# kiceker_board.net
KiCad netlist of a schematic drawn in EAGLE
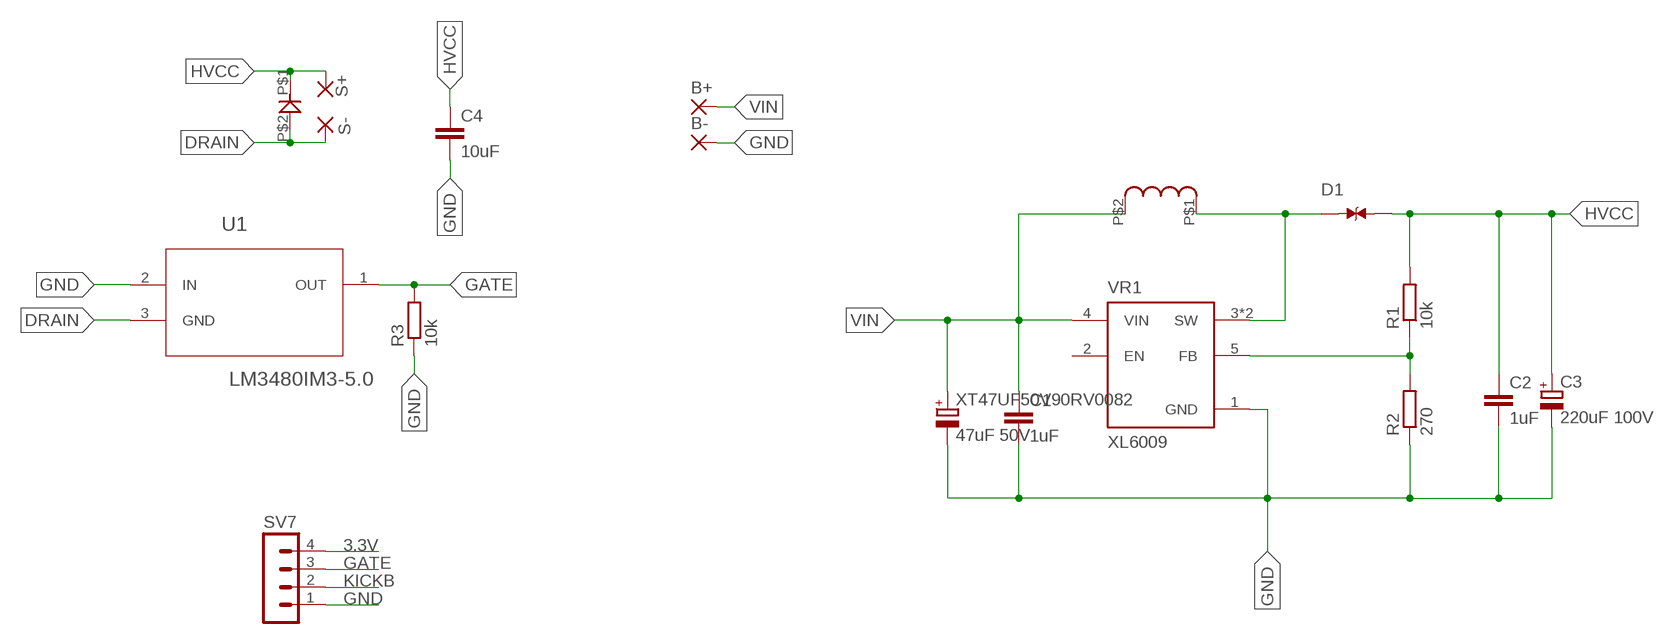
[diagram p0: schematic, sheet 1]

(export (version "E")
  (design (tool "Eeschema 10.0.6"))
  (components
    (comp (ref "B+")
      (value "3,81/1,4")
      (footprint "eagle-import:3,81_1,4")
      (libsource (lib "eagle-import") (part "3,81/1,4"))
    )
    (comp (ref "B-")
      (value "3,81/1,4")
      (footprint "eagle-import:3,81_1,4")
      (libsource (lib "eagle-import") (part "3,81/1,4"))
    )
    (comp (ref "C1")
      (value "1uF")
      (footprint "eagle-import:C0603")
      (libsource (lib "eagle-import") (part "C-EUC0603"))
    )
    (comp (ref "C2")
      (value "1uF")
      (footprint "eagle-import:C0603")
      (libsource (lib "eagle-import") (part "C-EUC0603"))
    )
    (comp (ref "C3")
      (value "220uF 100V")
      (footprint "eagle-import:E5-5")
      (libsource (lib "eagle-import") (part "CPOL-EUE5-5"))
    )
    (comp (ref "C4")
      (value "10uF")
      (footprint "eagle-import:C0603")
      (libsource (lib "eagle-import") (part "C-EUC0603"))
    )
    (comp (ref "D1")
      (value "SMCJ15CA_V7G")
      (footprint "eagle-import:DIOM6859X262N")
      (fields (field (name "MF") "Taiwan Semiconductor") (field (name "MP") "SMCJ15CA V7G"))
      (libsource (lib "eagle-import") (part "SMCJ15CA_V7G"))
    )
    (comp (ref "R1")
      (value "10k")
      (footprint "eagle-import:R0603")
      (libsource (lib "eagle-import") (part "R-EU_R0603"))
    )
    (comp (ref "R2")
      (value "270")
      (footprint "eagle-import:R0603")
      (libsource (lib "eagle-import") (part "R-EU_R0603"))
    )
    (comp (ref "R3")
      (value "10k")
      (footprint "eagle-import:R0603")
      (libsource (lib "eagle-import") (part "R-EU_R0603"))
    )
    (comp (ref "S+")
      (value "3,81/1,4")
      (footprint "eagle-import:3,81_1,4")
      (libsource (lib "eagle-import") (part "3,81/1,4"))
    )
    (comp (ref "S-")
      (value "3,81/1,4")
      (footprint "eagle-import:3,81_1,4")
      (libsource (lib "eagle-import") (part "3,81/1,4"))
    )
    (comp (ref "SV7")
      (value "MA04-1")
      (footprint "eagle-import:MA04-1")
      (libsource (lib "eagle-import") (part "MA04-1"))
    )
    (comp (ref "U$1")
      (value "TMPC1265")
      (footprint "eagle-import:TMPC1265")
      (libsource (lib "eagle-import") (part "TMPC1265"))
    )
    (comp (ref "U$2")
      (value "SMBF")
      (footprint "eagle-import:SMBF")
      (libsource (lib "eagle-import") (part "SMBF"))
    )
    (comp (ref "U1")
      (value "LM3480IM3-5.0")
      (footprint "eagle-import:SOT95P263X110-3N")
      (fields (field (name "MF") "Texas") (field (name "MP") "LM3480IM3-5.0/NOPB"))
      (libsource (lib "eagle-import") (part "LM3480IM3-5.0"))
    )
    (comp (ref "VR1")
      (value "XL6009")
      (footprint "eagle-import:DPAK170P1435X465-6N")
      (fields (field (name "MF") "XLSEMI"))
      (libsource (lib "eagle-import") (part "XL6009"))
    )
    (comp (ref "XT47UF50V90RV0082")
      (value "47uF 50V")
      (footprint "eagle-import:153CLV-0605")
      (libsource (lib "eagle-import") (part "CPOL-EU153CLV-0605"))
    )
  )
  (nets
    (net (code "1") (name "/3.3V") (class "Default")
      (node (ref "SV7") (pin "4") (pinfunction "4_4") (pintype "passive"))
    )
    (net (code "2") (name "/KICKB") (class "Default")
      (node (ref "SV7") (pin "2") (pinfunction "2_2") (pintype "passive"))
    )
    (net (code "3") (name "DRAIN") (class "Default")
      (node (ref "S-") (pin "1") (pinfunction "P_1") (pintype "passive"))
      (node (ref "U$2") (pin "P$2") (pinfunction "P$1_P$2") (pintype "bidirectional"))
      (node (ref "U1") (pin "3") (pinfunction "GND_3") (pintype "passive"))
    )
    (net (code "4") (name "GATE") (class "Default")
      (node (ref "R3") (pin "2") (pinfunction "2_2") (pintype "passive"))
      (node (ref "SV7") (pin "3") (pinfunction "3_3") (pintype "passive"))
      (node (ref "U1") (pin "1") (pinfunction "OUT_1") (pintype "output"))
    )
    (net (code "5") (name "GND") (class "Default")
      (node (ref "B-") (pin "1") (pinfunction "P_1") (pintype "passive"))
      (node (ref "C1") (pin "2") (pinfunction "2_2") (pintype "passive"))
      (node (ref "C2") (pin "2") (pinfunction "2_2") (pintype "passive"))
      (node (ref "C3") (pin "-") (pinfunction "-_-") (pintype "passive"))
      (node (ref "C4") (pin "2") (pinfunction "2_2") (pintype "passive"))
      (node (ref "R2") (pin "1") (pinfunction "1_1") (pintype "passive"))
      (node (ref "R3") (pin "1") (pinfunction "1_1") (pintype "passive"))
      (node (ref "SV7") (pin "1") (pinfunction "1_1") (pintype "passive"))
      (node (ref "U1") (pin "2") (pinfunction "IN_2") (pintype "power_in"))
      (node (ref "VR1") (pin "1") (pinfunction "GND_1") (pintype "power_in"))
      (node (ref "XT47UF50V90RV0082") (pin "-") (pinfunction "-_-") (pintype "passive"))
    )
    (net (code "6") (name "HVCC") (class "Default")
      (node (ref "C2") (pin "1") (pinfunction "1_1") (pintype "passive"))
      (node (ref "C3") (pin "+") (pinfunction "+_+") (pintype "passive"))
      (node (ref "C4") (pin "1") (pinfunction "1_1") (pintype "passive"))
      (node (ref "D1") (pin "2") (pinfunction "2_2") (pintype "passive"))
      (node (ref "R1") (pin "2") (pinfunction "2_2") (pintype "passive"))
      (node (ref "S+") (pin "1") (pinfunction "P_1") (pintype "passive"))
      (node (ref "U$2") (pin "P$1") (pinfunction "P$2_P$1") (pintype "bidirectional"))
    )
    (net (code "7") (name "Net-(U$1-P$2)") (class "Default")
      (node (ref "D1") (pin "1") (pinfunction "1_1") (pintype "passive"))
      (node (ref "U$1") (pin "P$1") (pinfunction "P$2_P$1") (pintype "bidirectional"))
      (node (ref "VR1") (pin "3") (pinfunction "SW_3") (pintype "output"))
      (node (ref "VR1") (pin "6") (pinfunction "SW_6") (pintype "output"))
    )
    (net (code "8") (name "Net-(VR1-FB)") (class "Default")
      (node (ref "R1") (pin "1") (pinfunction "1_1") (pintype "passive"))
      (node (ref "R2") (pin "2") (pinfunction "2_2") (pintype "passive"))
      (node (ref "VR1") (pin "5") (pinfunction "FB_5") (pintype "input"))
    )
    (net (code "9") (name "VIN") (class "Default")
      (node (ref "B+") (pin "1") (pinfunction "P_1") (pintype "passive"))
      (node (ref "C1") (pin "1") (pinfunction "1_1") (pintype "passive"))
      (node (ref "U$1") (pin "P$2") (pinfunction "P$1_P$2") (pintype "bidirectional"))
      (node (ref "VR1") (pin "4") (pinfunction "VIN_4") (pintype "input"))
      (node (ref "XT47UF50V90RV0082") (pin "+") (pinfunction "+_+") (pintype "passive"))
    )
    (net (code "10") (name "unconnected-(VR1-EN-Pad2)") (class "Default")
      (node (ref "VR1") (pin "2") (pinfunction "EN_2") (pintype "input"))
    )
  )
)
